# Lipo-Charger-Sch.net
KiCad netlist of a schematic drawn in Altium Designer
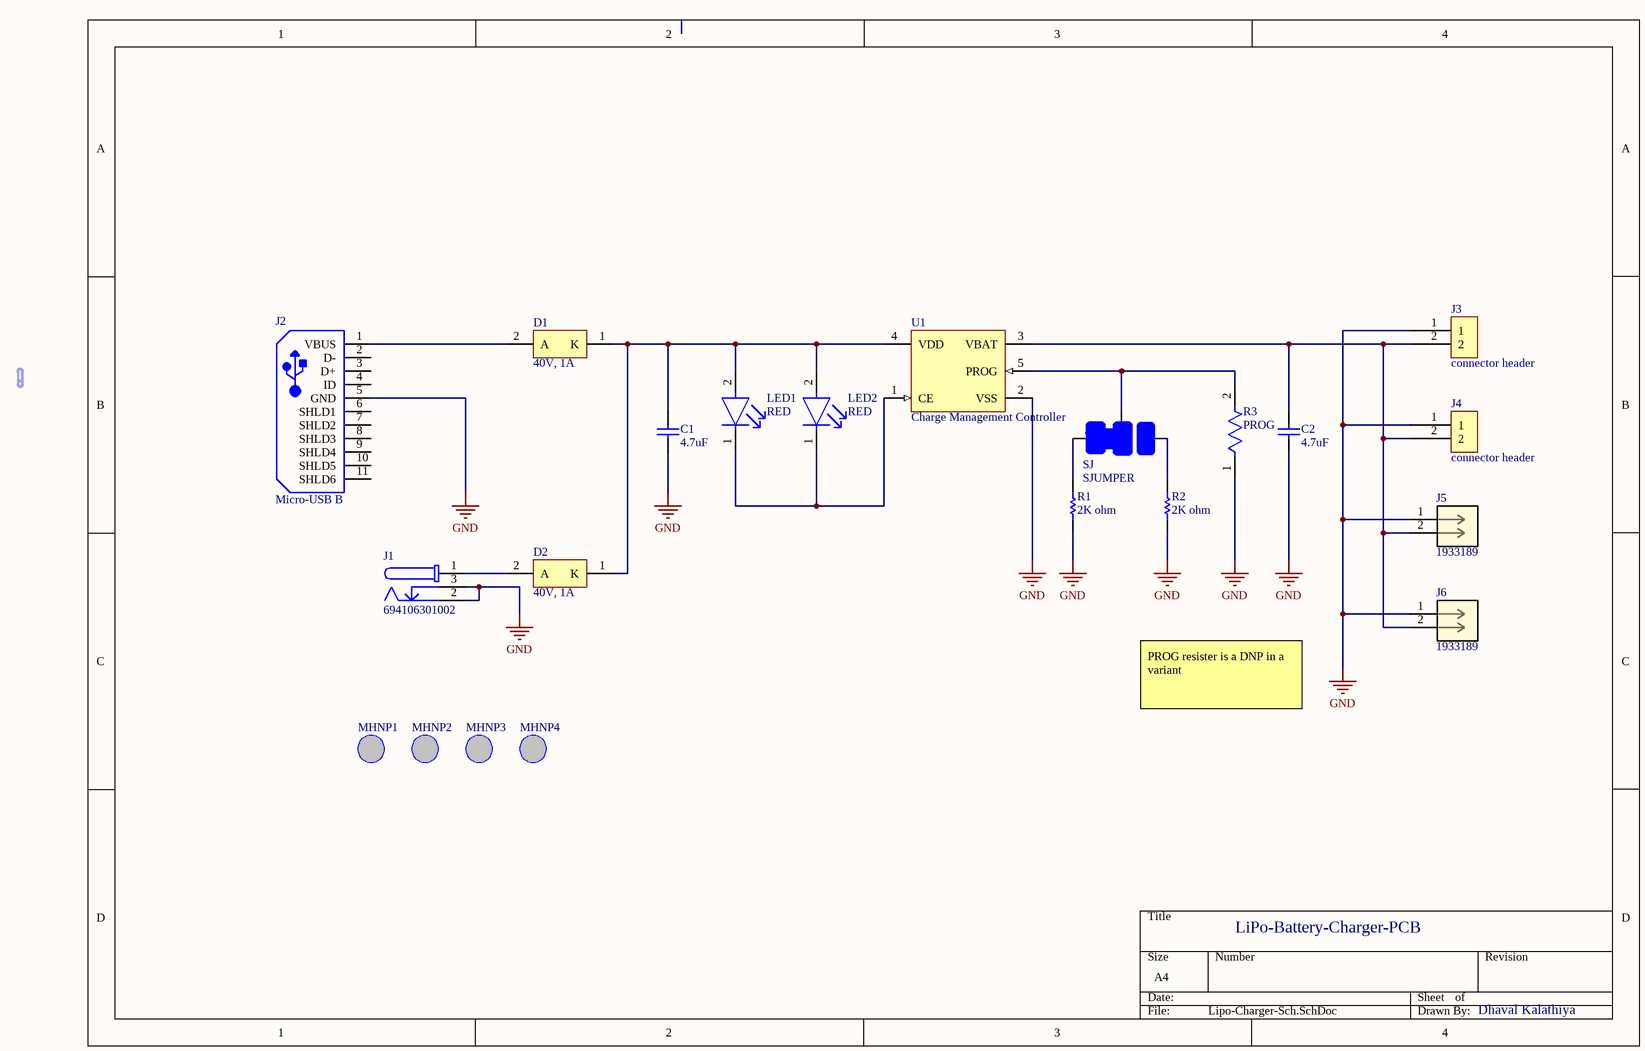
[diagram p0: Lipo-Charger-Sch.SchDoc]

(export (version "E")
  (design (tool "Eeschema 10.0.6"))
  (components
    (comp (ref "C1")
      (value "4.7uF")
      (footprint "CAPC1206(3216)150_M")
      (fields (field (name "TOLERANCE") "Â±5%"))
      (libsource (lib "Altium Content Vault") (part "CAP"))
    )
    (comp (ref "C2")
      (value "4.7uF")
      (footprint "CAPC1206(3216)150_M")
      (fields (field (name "TOLERANCE") "Â±5%"))
      (libsource (lib "Altium Content Vault") (part "CAP"))
    )
    (comp (ref "D1")
      (value "40V, 1A")
      (footprint "ONSC-SMA-2-403D-02_V")
      (description "Schottky Power Rectifier, 2-Pin SMA, Pb-Free, Tape and Reel")
      (fields (field (name "PARTNUMBER") "MBRA140T3G") (field (name "MANUFACTURER") "On Semiconductor"))
      (libsource (lib "Altium Content Vault") (part "ONSC-D-K1A2-2_A"))
    )
    (comp (ref "D2")
      (value "40V, 1A")
      (footprint "ONSC-SMA-2-403D-02_V")
      (description "Schottky Power Rectifier, 2-Pin SMA, Pb-Free, Tape and Reel")
      (fields (field (name "PARTNUMBER") "MBRA140T3G") (field (name "MANUFACTURER") "On Semiconductor"))
      (libsource (lib "Altium Content Vault") (part "ONSC-D-K1A2-2_A"))
    )
    (comp (ref "J1")
      (value "694106301002")
      (footprint "694106301002")
      (libsource (lib "Altium Content Vault") (part "DC Power Jack"))
    )
    (comp (ref "J2")
      (value "Micro-USB B")
      (footprint "USB-MICRO-B_V")
      (fields (field (name "MANUFACTURER") "Molex"))
      (libsource (lib "Altium Content Vault") (part "USB-5-6SHLD"))
    )
    (comp (ref "J3")
      (value "connector header")
      (footprint "2-179276-2")
      (fields (field (name "MANUFACTURE PART NUMBER") "2-179276-2"))
      (libsource (lib "Schlib1") (part "2-179276-2"))
    )
    (comp (ref "J4")
      (value "connector header")
      (footprint "2-179276-2")
      (fields (field (name "MANUFACTURE PART NUMBER") "2-179276-2"))
      (libsource (lib "Schlib1") (part "2-179276-2"))
    )
    (comp (ref "J5")
      (value "1933189")
      (footprint "CONN02_1933189_PXC")
      (description "No Description Available")
      (libsource (lib "Schlib1") (part "1933189"))
    )
    (comp (ref "J6")
      (value "1933189")
      (footprint "CONN02_1933189_PXC")
      (description "No Description Available")
      (libsource (lib "Schlib1") (part "1933189"))
    )
    (comp (ref "LED1")
      (value "RED")
      (footprint "FP-SML-LX0603IW-TR-MFG")
      (description "LED RED DIFFUSED SMD")
      (libsource (lib "Altium Content Vault") (part "8706943c75ba83719d021d2fdc84c58"))
    )
    (comp (ref "LED2")
      (value "RED")
      (footprint "FP-SML-LX0603IW-TR-MFG")
      (description "LED RED DIFFUSED SMD")
      (libsource (lib "Altium Content Vault") (part "8706943c75ba83719d021d2fdc84c58"))
    )
    (comp (ref "MHNP1")
      (value "Mounting Hole Non-Plated 3.2mm")
      (footprint "MTHNP3P2")
      (libsource (lib "Schlib1") (part "MTHNP3P2"))
    )
    (comp (ref "MHNP2")
      (value "Mounting Hole Non-Plated 3.2mm")
      (footprint "MTHNP3P2")
      (libsource (lib "Schlib1") (part "MTHNP3P2"))
    )
    (comp (ref "MHNP3")
      (value "Mounting Hole Non-Plated 3.2mm")
      (footprint "MTHNP3P2")
      (libsource (lib "Schlib1") (part "MTHNP3P2"))
    )
    (comp (ref "MHNP4")
      (value "Mounting Hole Non-Plated 3.2mm")
      (footprint "MTHNP3P2")
      (libsource (lib "Schlib1") (part "MTHNP3P2"))
    )
    (comp (ref "R1")
      (value "2K ohm")
      (footprint "RESC2013X70X40LL20T20")
      (fields (field (name "PART NUMBER") "ERJ-P06J202V") (field (name "MANUFACTURER") "Panasonic"))
      (libsource (lib "Altium Content Vault") (part "RES"))
    )
    (comp (ref "R2")
      (value "2K ohm")
      (footprint "RESC2013X70X40LL20T20")
      (fields (field (name "PART NUMBER") "ERJ-P06J202V") (field (name "MANUFACTURER") "Panasonic"))
      (libsource (lib "Altium Content Vault") (part "RES"))
    )
    (comp (ref "R3")
      (value "PROG")
      (footprint "FP-CMF50-0")
      (fields (field (name "TOLERANCE") "1%"))
      (libsource (lib "Altium Content Vault") (part "1029c3af85768c4190bb7ad29bc67b5"))
    )
    (comp (ref "SJ")
      (value "SJUMPER")
      (footprint "SJUMPER-Footprint-1")
      (description "solder jumper 3 pods and pins")
      (libsource (lib "Dhaval Kalathiya") (part "SJUMPER-Symbol-1"))
    )
    (comp (ref "U1")
      (value "Charge Management Controller")
      (footprint "SOT-23-OT5_M")
      (libsource (lib "Altium Content Vault") (part "PM-BM-MCP7381X-SOT5"))
    )
  )
  (nets
    (net (code "1") (name "GND") (class "Default")
      (node (ref "C1") (pin "1") (pinfunction "1_1") (pintype "passive"))
      (node (ref "C2") (pin "1") (pinfunction "1_1") (pintype "passive"))
      (node (ref "J1") (pin "2") (pinfunction "2_2") (pintype "passive"))
      (node (ref "J1") (pin "3") (pinfunction "3_3") (pintype "passive"))
      (node (ref "J2") (pin "5") (pinfunction "GND_5") (pintype "passive"))
      (node (ref "J3") (pin "1") (pinfunction "1_1") (pintype "passive"))
      (node (ref "J4") (pin "1") (pinfunction "1_1") (pintype "passive"))
      (node (ref "J5") (pin "1") (pinfunction "1_1") (pintype "passive"))
      (node (ref "J6") (pin "1") (pinfunction "1_1") (pintype "passive"))
      (node (ref "R1") (pin "1") (pinfunction "1_1") (pintype "passive"))
      (node (ref "R2") (pin "1") (pinfunction "1_1") (pintype "passive"))
      (node (ref "R3") (pin "1") (pinfunction "1_1") (pintype "passive"))
      (node (ref "U1") (pin "2") (pinfunction "VSS_2") (pintype "power_in"))
    )
    (net (code "2") (name "Net-(D1-A)") (class "Default")
      (node (ref "D1") (pin "2") (pinfunction "A_2") (pintype "passive"))
      (node (ref "J2") (pin "1") (pinfunction "VBUS_1") (pintype "passive"))
    )
    (net (code "3") (name "Net-(D1-K)") (class "Default")
      (node (ref "C1") (pin "2") (pinfunction "2_2") (pintype "passive"))
      (node (ref "D1") (pin "1") (pinfunction "K_1") (pintype "passive"))
      (node (ref "D2") (pin "1") (pinfunction "K_1") (pintype "passive"))
      (node (ref "LED1") (pin "2") (pinfunction "A_2") (pintype "passive"))
      (node (ref "LED2") (pin "2") (pinfunction "A_2") (pintype "passive"))
      (node (ref "U1") (pin "4") (pinfunction "VDD_4") (pintype "power_in"))
    )
    (net (code "4") (name "Net-(D2-A)") (class "Default")
      (node (ref "D2") (pin "2") (pinfunction "A_2") (pintype "passive"))
      (node (ref "J1") (pin "1") (pinfunction "1_1") (pintype "passive"))
    )
    (net (code "5") (name "Net-(LED1-C)") (class "Default")
      (node (ref "LED1") (pin "1") (pinfunction "C_1") (pintype "passive"))
      (node (ref "LED2") (pin "1") (pinfunction "C_1") (pintype "passive"))
      (node (ref "U1") (pin "1") (pinfunction "CE_1") (pintype "input"))
    )
    (net (code "6") (name "Net-(R1-Pad2)") (class "Default")
      (node (ref "R1") (pin "2") (pinfunction "2_2") (pintype "passive"))
      (node (ref "SJ") (pin "1") (pinfunction "1_1") (pintype "passive"))
    )
    (net (code "7") (name "Net-(R2-Pad2)") (class "Default")
      (node (ref "R2") (pin "2") (pinfunction "2_2") (pintype "passive"))
      (node (ref "SJ") (pin "3") (pinfunction "3_3") (pintype "passive"))
    )
    (net (code "8") (name "Net-(U1-PROG)") (class "Default")
      (node (ref "R3") (pin "2") (pinfunction "2_2") (pintype "passive"))
      (node (ref "SJ") (pin "2") (pinfunction "2_2") (pintype "passive"))
      (node (ref "U1") (pin "5") (pinfunction "PROG_5") (pintype "input"))
    )
    (net (code "9") (name "Net-(U1-VBAT)") (class "Default")
      (node (ref "C2") (pin "2") (pinfunction "2_2") (pintype "passive"))
      (node (ref "J3") (pin "2") (pinfunction "2_2") (pintype "passive"))
      (node (ref "J4") (pin "2") (pinfunction "2_2") (pintype "passive"))
      (node (ref "J5") (pin "2") (pinfunction "2_2") (pintype "passive"))
      (node (ref "J6") (pin "2") (pinfunction "2_2") (pintype "passive"))
      (node (ref "U1") (pin "3") (pinfunction "VBAT_3") (pintype "power_in"))
    )
    (net (code "10") (name "unconnected-(J2-D+-Pad3)") (class "Default")
      (node (ref "J2") (pin "3") (pinfunction "D+_3") (pintype "passive"))
    )
    (net (code "11") (name "unconnected-(J2-D--Pad2)") (class "Default")
      (node (ref "J2") (pin "2") (pinfunction "D-_2") (pintype "passive"))
    )
    (net (code "12") (name "unconnected-(J2-ID-Pad4)") (class "Default")
      (node (ref "J2") (pin "4") (pinfunction "ID_4") (pintype "passive"))
    )
    (net (code "13") (name "unconnected-(J2-SHLD1-Pad6)") (class "Default")
      (node (ref "J2") (pin "6") (pinfunction "SHLD1_6") (pintype "passive"))
    )
    (net (code "14") (name "unconnected-(J2-SHLD2-Pad7)") (class "Default")
      (node (ref "J2") (pin "7") (pinfunction "SHLD2_7") (pintype "passive"))
    )
    (net (code "15") (name "unconnected-(J2-SHLD3-Pad8)") (class "Default")
      (node (ref "J2") (pin "8") (pinfunction "SHLD3_8") (pintype "passive"))
    )
    (net (code "16") (name "unconnected-(J2-SHLD4-Pad9)") (class "Default")
      (node (ref "J2") (pin "9") (pinfunction "SHLD4_9") (pintype "passive"))
    )
    (net (code "17") (name "unconnected-(J2-SHLD5-Pad10)") (class "Default")
      (node (ref "J2") (pin "10") (pinfunction "SHLD5_10") (pintype "passive"))
    )
    (net (code "18") (name "unconnected-(J2-SHLD6-Pad11)") (class "Default")
      (node (ref "J2") (pin "11") (pinfunction "SHLD6_11") (pintype "passive"))
    )
  )
)
